# fpc_adapter.net
KiCad netlist of a schematic drawn in EAGLE
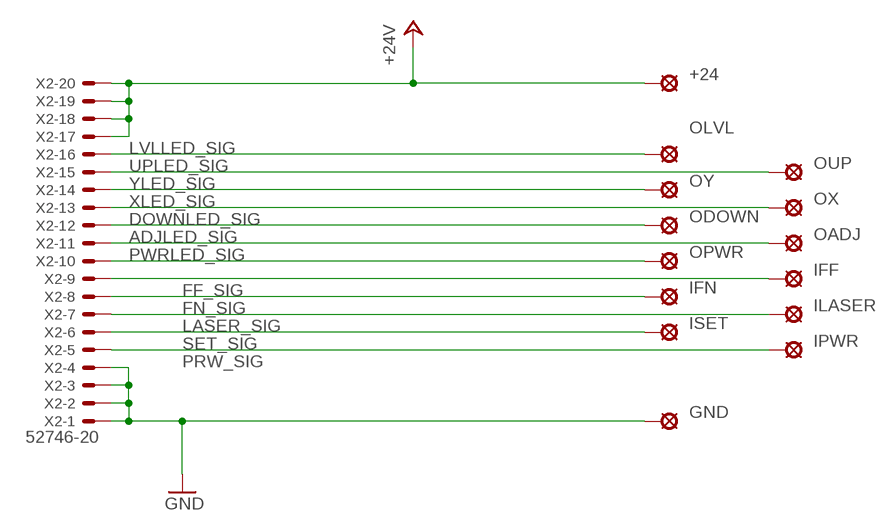
[diagram p0: schematic, sheet 1]

(export (version "E")
  (design (tool "Eeschema 10.0.6"))
  (components
    (comp (ref "+24")
      (value "LSP10")
      (footprint "eagle-import:LSP10")
      (libsource (lib "eagle-import") (part "LSP10"))
    )
    (comp (ref "GND")
      (value "LSP10")
      (footprint "eagle-import:LSP10")
      (libsource (lib "eagle-import") (part "LSP10"))
    )
    (comp (ref "IFF")
      (value "LSP10")
      (footprint "eagle-import:LSP10")
      (libsource (lib "eagle-import") (part "LSP10"))
    )
    (comp (ref "IFN")
      (value "LSP10")
      (footprint "eagle-import:LSP10")
      (libsource (lib "eagle-import") (part "LSP10"))
    )
    (comp (ref "ILASER")
      (value "LSP10")
      (footprint "eagle-import:LSP10")
      (libsource (lib "eagle-import") (part "LSP10"))
    )
    (comp (ref "IPWR")
      (value "LSP10")
      (footprint "eagle-import:LSP10")
      (libsource (lib "eagle-import") (part "LSP10"))
    )
    (comp (ref "ISET")
      (value "LSP10")
      (footprint "eagle-import:LSP10")
      (libsource (lib "eagle-import") (part "LSP10"))
    )
    (comp (ref "OADJ")
      (value "LSP10")
      (footprint "eagle-import:LSP10")
      (libsource (lib "eagle-import") (part "LSP10"))
    )
    (comp (ref "ODOWN")
      (value "LSP10")
      (footprint "eagle-import:LSP10")
      (libsource (lib "eagle-import") (part "LSP10"))
    )
    (comp (ref "OLVL")
      (value "LSP10")
      (footprint "eagle-import:LSP10")
      (libsource (lib "eagle-import") (part "LSP10"))
    )
    (comp (ref "OPWR")
      (value "LSP10")
      (footprint "eagle-import:LSP10")
      (libsource (lib "eagle-import") (part "LSP10"))
    )
    (comp (ref "OUP")
      (value "LSP10")
      (footprint "eagle-import:LSP10")
      (libsource (lib "eagle-import") (part "LSP10"))
    )
    (comp (ref "OX")
      (value "LSP10")
      (footprint "eagle-import:LSP10")
      (libsource (lib "eagle-import") (part "LSP10"))
    )
    (comp (ref "OY")
      (value "LSP10")
      (footprint "eagle-import:LSP10")
      (libsource (lib "eagle-import") (part "LSP10"))
    )
    (comp (ref "X2")
      (value "52746-20")
      (footprint "eagle-import:52746-20")
      (fields (field (name "MF") "MOLEX"))
      (libsource (lib "eagle-import") (part "52746-20"))
    )
  )
  (nets
    (net (code "1") (name "+24V") (class "Default")
      (node (ref "+24") (pin "MP") (pinfunction "MP_MP") (pintype "passive"))
      (node (ref "X2") (pin "17") (pinfunction "S_17") (pintype "passive"))
      (node (ref "X2") (pin "18") (pinfunction "S_18") (pintype "passive"))
      (node (ref "X2") (pin "19") (pinfunction "S_19") (pintype "passive"))
      (node (ref "X2") (pin "20") (pinfunction "S_20") (pintype "passive"))
    )
    (net (code "2") (name "/ADJLED_SIG") (class "Default")
      (node (ref "OADJ") (pin "MP") (pinfunction "MP_MP") (pintype "passive"))
      (node (ref "X2") (pin "11") (pinfunction "S_11") (pintype "passive"))
    )
    (net (code "3") (name "/DOWNLED_SIG") (class "Default")
      (node (ref "ODOWN") (pin "MP") (pinfunction "MP_MP") (pintype "passive"))
      (node (ref "X2") (pin "12") (pinfunction "S_12") (pintype "passive"))
    )
    (net (code "4") (name "/FF_SIG") (class "Default")
      (node (ref "IFF") (pin "MP") (pinfunction "MP_MP") (pintype "passive"))
      (node (ref "X2") (pin "9") (pinfunction "S_9") (pintype "passive"))
    )
    (net (code "5") (name "/FN_SIG") (class "Default")
      (node (ref "IFN") (pin "MP") (pinfunction "MP_MP") (pintype "passive"))
      (node (ref "X2") (pin "8") (pinfunction "S_8") (pintype "passive"))
    )
    (net (code "6") (name "/LASER_SIG") (class "Default")
      (node (ref "ILASER") (pin "MP") (pinfunction "MP_MP") (pintype "passive"))
      (node (ref "X2") (pin "7") (pinfunction "S_7") (pintype "passive"))
    )
    (net (code "7") (name "/LVLLED_SIG") (class "Default")
      (node (ref "OLVL") (pin "MP") (pinfunction "MP_MP") (pintype "passive"))
      (node (ref "X2") (pin "16") (pinfunction "S_16") (pintype "passive"))
    )
    (net (code "8") (name "/PRW_SIG") (class "Default")
      (node (ref "IPWR") (pin "MP") (pinfunction "MP_MP") (pintype "passive"))
      (node (ref "X2") (pin "5") (pinfunction "S_5") (pintype "passive"))
    )
    (net (code "9") (name "/PWRLED_SIG") (class "Default")
      (node (ref "OPWR") (pin "MP") (pinfunction "MP_MP") (pintype "passive"))
      (node (ref "X2") (pin "10") (pinfunction "S_10") (pintype "passive"))
    )
    (net (code "10") (name "/SET_SIG") (class "Default")
      (node (ref "ISET") (pin "MP") (pinfunction "MP_MP") (pintype "passive"))
      (node (ref "X2") (pin "6") (pinfunction "S_6") (pintype "passive"))
    )
    (net (code "11") (name "/UPLED_SIG") (class "Default")
      (node (ref "OUP") (pin "MP") (pinfunction "MP_MP") (pintype "passive"))
      (node (ref "X2") (pin "15") (pinfunction "S_15") (pintype "passive"))
    )
    (net (code "12") (name "/XLED_SIG") (class "Default")
      (node (ref "OX") (pin "MP") (pinfunction "MP_MP") (pintype "passive"))
      (node (ref "X2") (pin "13") (pinfunction "S_13") (pintype "passive"))
    )
    (net (code "13") (name "/YLED_SIG") (class "Default")
      (node (ref "OY") (pin "MP") (pinfunction "MP_MP") (pintype "passive"))
      (node (ref "X2") (pin "14") (pinfunction "S_14") (pintype "passive"))
    )
    (net (code "14") (name "GND") (class "Default")
      (node (ref "GND") (pin "MP") (pinfunction "MP_MP") (pintype "passive"))
      (node (ref "X2") (pin "1") (pinfunction "S_1") (pintype "passive"))
      (node (ref "X2") (pin "2") (pinfunction "S_2") (pintype "passive"))
      (node (ref "X2") (pin "3") (pinfunction "S_3") (pintype "passive"))
      (node (ref "X2") (pin "4") (pinfunction "S_4") (pintype "passive"))
    )
  )
)
